# rf_connection_sch4.net
KiCad netlist of a schematic drawn in Altium Designer
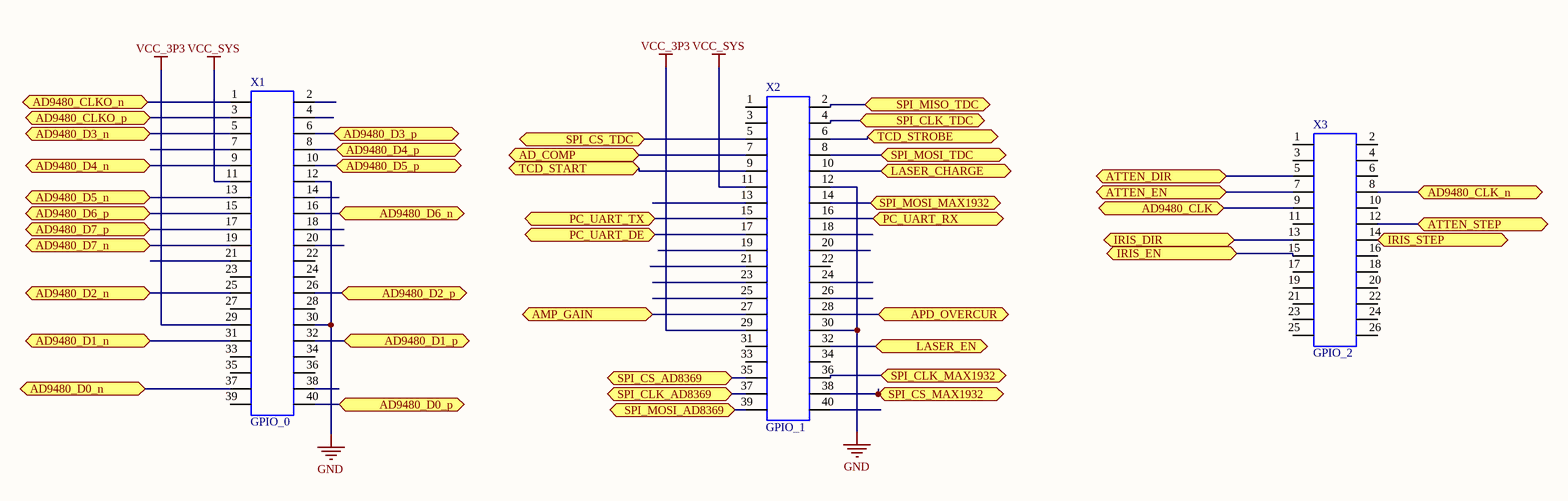
[diagram p0: rf_connection_sch4.SchDoc]

(export (version "E")
  (design (tool "Eeschema 10.0.6"))
  (components
    (comp (ref "X1") (value "GPIO_0") (libsource (lib "Connectors") (part "40pin_2x")))
    (comp (ref "X2") (value "GPIO_1") (libsource (lib "Connectors") (part "40pin_2x")))
    (comp (ref "X3") (value "GPIO_2") (libsource (lib "Connectors") (part "26pin_2x")))
  )
  (nets
    (net (code "1") (name "/AD9480_CLK") (class "Default")
      (node (ref "X3") (pin "9") (pinfunction "9_9") (pintype "passive"))
    )
    (net (code "2") (name "/AD9480_CLKO_n") (class "Default")
      (node (ref "X1") (pin "1") (pinfunction "1_1") (pintype "passive"))
    )
    (net (code "3") (name "/AD9480_CLKO_p") (class "Default")
      (node (ref "X1") (pin "3") (pinfunction "3_3") (pintype "passive"))
    )
    (net (code "4") (name "/AD9480_CLK_n") (class "Default")
      (node (ref "X3") (pin "8") (pinfunction "8_8") (pintype "passive"))
    )
    (net (code "5") (name "/AD9480_D0_n") (class "Default")
      (node (ref "X1") (pin "37") (pinfunction "37_37") (pintype "passive"))
    )
    (net (code "6") (name "/AD9480_D0_p") (class "Default")
      (node (ref "X1") (pin "40") (pinfunction "40_40") (pintype "passive"))
    )
    (net (code "7") (name "/AD9480_D1_n") (class "Default")
      (node (ref "X1") (pin "31") (pinfunction "31_31") (pintype "passive"))
    )
    (net (code "8") (name "/AD9480_D1_p") (class "Default")
      (node (ref "X1") (pin "32") (pinfunction "32_32") (pintype "passive"))
    )
    (net (code "9") (name "/AD9480_D2_n") (class "Default")
      (node (ref "X1") (pin "25") (pinfunction "25_25") (pintype "passive"))
    )
    (net (code "10") (name "/AD9480_D2_p") (class "Default")
      (node (ref "X1") (pin "26") (pinfunction "26_26") (pintype "passive"))
    )
    (net (code "11") (name "/AD9480_D3_n") (class "Default")
      (node (ref "X1") (pin "5") (pinfunction "5_5") (pintype "passive"))
    )
    (net (code "12") (name "/AD9480_D3_p") (class "Default")
      (node (ref "X1") (pin "6") (pinfunction "6_6") (pintype "passive"))
    )
    (net (code "13") (name "/AD9480_D4_n") (class "Default")
      (node (ref "X1") (pin "9") (pinfunction "9_9") (pintype "passive"))
    )
    (net (code "14") (name "/AD9480_D4_p") (class "Default")
      (node (ref "X1") (pin "8") (pinfunction "8_8") (pintype "passive"))
    )
    (net (code "15") (name "/AD9480_D5_n") (class "Default")
      (node (ref "X1") (pin "13") (pinfunction "13_13") (pintype "passive"))
    )
    (net (code "16") (name "/AD9480_D5_p") (class "Default")
      (node (ref "X1") (pin "10") (pinfunction "10_10") (pintype "passive"))
    )
    (net (code "17") (name "/AD9480_D6_n") (class "Default")
      (node (ref "X1") (pin "16") (pinfunction "16_16") (pintype "passive"))
    )
    (net (code "18") (name "/AD9480_D6_p") (class "Default")
      (node (ref "X1") (pin "15") (pinfunction "15_15") (pintype "passive"))
    )
    (net (code "19") (name "/AD9480_D7_n") (class "Default")
      (node (ref "X1") (pin "19") (pinfunction "19_19") (pintype "passive"))
    )
    (net (code "20") (name "/AD9480_D7_p") (class "Default")
      (node (ref "X1") (pin "17") (pinfunction "17_17") (pintype "passive"))
    )
    (net (code "21") (name "/AD_COMP") (class "Default")
      (node (ref "X2") (pin "7") (pinfunction "7_7") (pintype "passive"))
    )
    (net (code "22") (name "/AMP_GAIN") (class "Default")
      (node (ref "X2") (pin "27") (pinfunction "27_27") (pintype "passive"))
    )
    (net (code "23") (name "/APD_OVERCUR") (class "Default")
      (node (ref "X2") (pin "28") (pinfunction "28_28") (pintype "passive"))
    )
    (net (code "24") (name "/ATTEN_DIR") (class "Default")
      (node (ref "X3") (pin "5") (pinfunction "5_5") (pintype "passive"))
    )
    (net (code "25") (name "/ATTEN_EN") (class "Default")
      (node (ref "X3") (pin "7") (pinfunction "7_7") (pintype "passive"))
    )
    (net (code "26") (name "/ATTEN_STEP") (class "Default")
      (node (ref "X3") (pin "12") (pinfunction "12_12") (pintype "passive"))
    )
    (net (code "27") (name "/IRIS_DIR") (class "Default")
      (node (ref "X3") (pin "13") (pinfunction "13_13") (pintype "passive"))
    )
    (net (code "28") (name "/IRIS_EN") (class "Default")
      (node (ref "X3") (pin "15") (pinfunction "15_15") (pintype "passive"))
    )
    (net (code "29") (name "/IRIS_STEP") (class "Default")
      (node (ref "X3") (pin "14") (pinfunction "14_14") (pintype "passive"))
    )
    (net (code "30") (name "/LASER_CHARGE") (class "Default")
      (node (ref "X2") (pin "10") (pinfunction "10_10") (pintype "passive"))
    )
    (net (code "31") (name "/LASER_EN") (class "Default")
      (node (ref "X2") (pin "32") (pinfunction "32_32") (pintype "passive"))
    )
    (net (code "32") (name "/PC_UART_DE") (class "Default")
      (node (ref "X2") (pin "17") (pinfunction "17_17") (pintype "passive"))
    )
    (net (code "33") (name "/PC_UART_RX") (class "Default")
      (node (ref "X2") (pin "16") (pinfunction "16_16") (pintype "passive"))
    )
    (net (code "34") (name "/PC_UART_TX") (class "Default")
      (node (ref "X2") (pin "15") (pinfunction "15_15") (pintype "passive"))
    )
    (net (code "35") (name "/SPI_CLK_AD8369") (class "Default")
      (node (ref "X2") (pin "37") (pinfunction "37_37") (pintype "passive"))
    )
    (net (code "36") (name "/SPI_CLK_MAX1932") (class "Default")
      (node (ref "X2") (pin "36") (pinfunction "36_36") (pintype "passive"))
    )
    (net (code "37") (name "/SPI_CLK_TDC") (class "Default")
      (node (ref "X2") (pin "4") (pinfunction "4_4") (pintype "passive"))
    )
    (net (code "38") (name "/SPI_CS_AD8369") (class "Default")
      (node (ref "X2") (pin "35") (pinfunction "35_35") (pintype "passive"))
    )
    (net (code "39") (name "/SPI_CS_MAX1932") (class "Default")
      (node (ref "X2") (pin "38") (pinfunction "38_38") (pintype "passive"))
    )
    (net (code "40") (name "/SPI_CS_TDC") (class "Default")
      (node (ref "X2") (pin "5") (pinfunction "5_5") (pintype "passive"))
    )
    (net (code "41") (name "/SPI_MISO_TDC") (class "Default")
      (node (ref "X2") (pin "2") (pinfunction "2_2") (pintype "passive"))
    )
    (net (code "42") (name "/SPI_MOSI_AD8369") (class "Default")
      (node (ref "X2") (pin "39") (pinfunction "39_39") (pintype "passive"))
    )
    (net (code "43") (name "/SPI_MOSI_MAX1932") (class "Default")
      (node (ref "X2") (pin "14") (pinfunction "14_14") (pintype "passive"))
    )
    (net (code "44") (name "/SPI_MOSI_TDC") (class "Default")
      (node (ref "X2") (pin "8") (pinfunction "8_8") (pintype "passive"))
    )
    (net (code "45") (name "/TCD_START") (class "Default")
      (node (ref "X2") (pin "9") (pinfunction "9_9") (pintype "passive"))
    )
    (net (code "46") (name "/TCD_STROBE") (class "Default")
      (node (ref "X2") (pin "6") (pinfunction "6_6") (pintype "passive"))
    )
    (net (code "47") (name "GND") (class "Default")
      (node (ref "X1") (pin "12") (pinfunction "12_12") (pintype "passive"))
      (node (ref "X1") (pin "30") (pinfunction "30_30") (pintype "passive"))
      (node (ref "X2") (pin "12") (pinfunction "12_12") (pintype "passive"))
      (node (ref "X2") (pin "30") (pinfunction "30_30") (pintype "passive"))
    )
    (net (code "48") (name "VCC_3P3") (class "Default")
      (node (ref "X1") (pin "29") (pinfunction "29_29") (pintype "passive"))
      (node (ref "X2") (pin "29") (pinfunction "29_29") (pintype "passive"))
    )
    (net (code "49") (name "VCC_SYS") (class "Default")
      (node (ref "X1") (pin "11") (pinfunction "11_11") (pintype "passive"))
      (node (ref "X2") (pin "11") (pinfunction "11_11") (pintype "passive"))
    )
    (net (code "50") (name "unconnected-(X1-Pad2)") (class "Default")
      (node (ref "X1") (pin "2") (pinfunction "2_2") (pintype "passive"))
    )
    (net (code "51") (name "unconnected-(X1-Pad4)") (class "Default")
      (node (ref "X1") (pin "4") (pinfunction "4_4") (pintype "passive"))
    )
    (net (code "52") (name "unconnected-(X1-Pad7)") (class "Default")
      (node (ref "X1") (pin "7") (pinfunction "7_7") (pintype "passive"))
    )
    (net (code "53") (name "unconnected-(X1-Pad14)") (class "Default")
      (node (ref "X1") (pin "14") (pinfunction "14_14") (pintype "passive"))
    )
    (net (code "54") (name "unconnected-(X1-Pad18)") (class "Default")
      (node (ref "X1") (pin "18") (pinfunction "18_18") (pintype "passive"))
    )
    (net (code "55") (name "unconnected-(X1-Pad20)") (class "Default")
      (node (ref "X1") (pin "20") (pinfunction "20_20") (pintype "passive"))
    )
    (net (code "56") (name "unconnected-(X1-Pad21)") (class "Default")
      (node (ref "X1") (pin "21") (pinfunction "21_21") (pintype "passive"))
    )
    (net (code "57") (name "unconnected-(X1-Pad22)") (class "Default")
      (node (ref "X1") (pin "22") (pinfunction "22_22") (pintype "passive"))
    )
    (net (code "58") (name "unconnected-(X1-Pad23)") (class "Default")
      (node (ref "X1") (pin "23") (pinfunction "23_23") (pintype "passive"))
    )
    (net (code "59") (name "unconnected-(X1-Pad24)") (class "Default")
      (node (ref "X1") (pin "24") (pinfunction "24_24") (pintype "passive"))
    )
    (net (code "60") (name "unconnected-(X1-Pad27)") (class "Default")
      (node (ref "X1") (pin "27") (pinfunction "27_27") (pintype "passive"))
    )
    (net (code "61") (name "unconnected-(X1-Pad28)") (class "Default")
      (node (ref "X1") (pin "28") (pinfunction "28_28") (pintype "passive"))
    )
    (net (code "62") (name "unconnected-(X1-Pad33)") (class "Default")
      (node (ref "X1") (pin "33") (pinfunction "33_33") (pintype "passive"))
    )
    (net (code "63") (name "unconnected-(X1-Pad34)") (class "Default")
      (node (ref "X1") (pin "34") (pinfunction "34_34") (pintype "passive"))
    )
    (net (code "64") (name "unconnected-(X1-Pad35)") (class "Default")
      (node (ref "X1") (pin "35") (pinfunction "35_35") (pintype "passive"))
    )
    (net (code "65") (name "unconnected-(X1-Pad36)") (class "Default")
      (node (ref "X1") (pin "36") (pinfunction "36_36") (pintype "passive"))
    )
    (net (code "66") (name "unconnected-(X1-Pad38)") (class "Default")
      (node (ref "X1") (pin "38") (pinfunction "38_38") (pintype "passive"))
    )
    (net (code "67") (name "unconnected-(X1-Pad39)") (class "Default")
      (node (ref "X1") (pin "39") (pinfunction "39_39") (pintype "passive"))
    )
    (net (code "68") (name "unconnected-(X2-Pad1)") (class "Default")
      (node (ref "X2") (pin "1") (pinfunction "1_1") (pintype "passive"))
    )
    (net (code "69") (name "unconnected-(X2-Pad3)") (class "Default")
      (node (ref "X2") (pin "3") (pinfunction "3_3") (pintype "passive"))
    )
    (net (code "70") (name "unconnected-(X2-Pad13)") (class "Default")
      (node (ref "X2") (pin "13") (pinfunction "13_13") (pintype "passive"))
    )
    (net (code "71") (name "unconnected-(X2-Pad18)") (class "Default")
      (node (ref "X2") (pin "18") (pinfunction "18_18") (pintype "passive"))
    )
    (net (code "72") (name "unconnected-(X2-Pad19)") (class "Default")
      (node (ref "X2") (pin "19") (pinfunction "19_19") (pintype "passive"))
    )
    (net (code "73") (name "unconnected-(X2-Pad20)") (class "Default")
      (node (ref "X2") (pin "20") (pinfunction "20_20") (pintype "passive"))
    )
    (net (code "74") (name "unconnected-(X2-Pad21)") (class "Default")
      (node (ref "X2") (pin "21") (pinfunction "21_21") (pintype "passive"))
    )
    (net (code "75") (name "unconnected-(X2-Pad22)") (class "Default")
      (node (ref "X2") (pin "22") (pinfunction "22_22") (pintype "passive"))
    )
    (net (code "76") (name "unconnected-(X2-Pad23)") (class "Default")
      (node (ref "X2") (pin "23") (pinfunction "23_23") (pintype "passive"))
    )
    (net (code "77") (name "unconnected-(X2-Pad24)") (class "Default")
      (node (ref "X2") (pin "24") (pinfunction "24_24") (pintype "passive"))
    )
    (net (code "78") (name "unconnected-(X2-Pad25)") (class "Default")
      (node (ref "X2") (pin "25") (pinfunction "25_25") (pintype "passive"))
    )
    (net (code "79") (name "unconnected-(X2-Pad26)") (class "Default")
      (node (ref "X2") (pin "26") (pinfunction "26_26") (pintype "passive"))
    )
    (net (code "80") (name "unconnected-(X2-Pad31)") (class "Default")
      (node (ref "X2") (pin "31") (pinfunction "31_31") (pintype "passive"))
    )
    (net (code "81") (name "unconnected-(X2-Pad33)") (class "Default")
      (node (ref "X2") (pin "33") (pinfunction "33_33") (pintype "passive"))
    )
    (net (code "82") (name "unconnected-(X2-Pad34)") (class "Default")
      (node (ref "X2") (pin "34") (pinfunction "34_34") (pintype "passive"))
    )
    (net (code "83") (name "unconnected-(X2-Pad40)") (class "Default")
      (node (ref "X2") (pin "40") (pinfunction "40_40") (pintype "passive"))
    )
    (net (code "84") (name "unconnected-(X3-Pad1)") (class "Default")
      (node (ref "X3") (pin "1") (pinfunction "1_1") (pintype "passive"))
    )
    (net (code "85") (name "unconnected-(X3-Pad2)") (class "Default")
      (node (ref "X3") (pin "2") (pinfunction "2_2") (pintype "passive"))
    )
    (net (code "86") (name "unconnected-(X3-Pad3)") (class "Default")
      (node (ref "X3") (pin "3") (pinfunction "3_3") (pintype "passive"))
    )
    (net (code "87") (name "unconnected-(X3-Pad4)") (class "Default")
      (node (ref "X3") (pin "4") (pinfunction "4_4") (pintype "passive"))
    )
    (net (code "88") (name "unconnected-(X3-Pad6)") (class "Default")
      (node (ref "X3") (pin "6") (pinfunction "6_6") (pintype "passive"))
    )
    (net (code "89") (name "unconnected-(X3-Pad10)") (class "Default")
      (node (ref "X3") (pin "10") (pinfunction "10_10") (pintype "passive"))
    )
    (net (code "90") (name "unconnected-(X3-Pad11)") (class "Default")
      (node (ref "X3") (pin "11") (pinfunction "11_11") (pintype "passive"))
    )
    (net (code "91") (name "unconnected-(X3-Pad16)") (class "Default")
      (node (ref "X3") (pin "16") (pinfunction "16_16") (pintype "passive"))
    )
    (net (code "92") (name "unconnected-(X3-Pad17)") (class "Default")
      (node (ref "X3") (pin "17") (pinfunction "17_17") (pintype "passive"))
    )
    (net (code "93") (name "unconnected-(X3-Pad18)") (class "Default")
      (node (ref "X3") (pin "18") (pinfunction "18_18") (pintype "passive"))
    )
    (net (code "94") (name "unconnected-(X3-Pad19)") (class "Default")
      (node (ref "X3") (pin "19") (pinfunction "19_19") (pintype "passive"))
    )
    (net (code "95") (name "unconnected-(X3-Pad20)") (class "Default")
      (node (ref "X3") (pin "20") (pinfunction "20_20") (pintype "passive"))
    )
    (net (code "96") (name "unconnected-(X3-Pad21)") (class "Default")
      (node (ref "X3") (pin "21") (pinfunction "21_21") (pintype "passive"))
    )
    (net (code "97") (name "unconnected-(X3-Pad22)") (class "Default")
      (node (ref "X3") (pin "22") (pinfunction "22_22") (pintype "passive"))
    )
    (net (code "98") (name "unconnected-(X3-Pad23)") (class "Default")
      (node (ref "X3") (pin "23") (pinfunction "23_23") (pintype "passive"))
    )
    (net (code "99") (name "unconnected-(X3-Pad24)") (class "Default")
      (node (ref "X3") (pin "24") (pinfunction "24_24") (pintype "passive"))
    )
    (net (code "100") (name "unconnected-(X3-Pad25)") (class "Default")
      (node (ref "X3") (pin "25") (pinfunction "25_25") (pintype "passive"))
    )
    (net (code "101") (name "unconnected-(X3-Pad26)") (class "Default")
      (node (ref "X3") (pin "26") (pinfunction "26_26") (pintype "passive"))
    )
  )
)
